# T09_LockBox_ver5.net
KiCad netlist of a schematic drawn in EAGLE
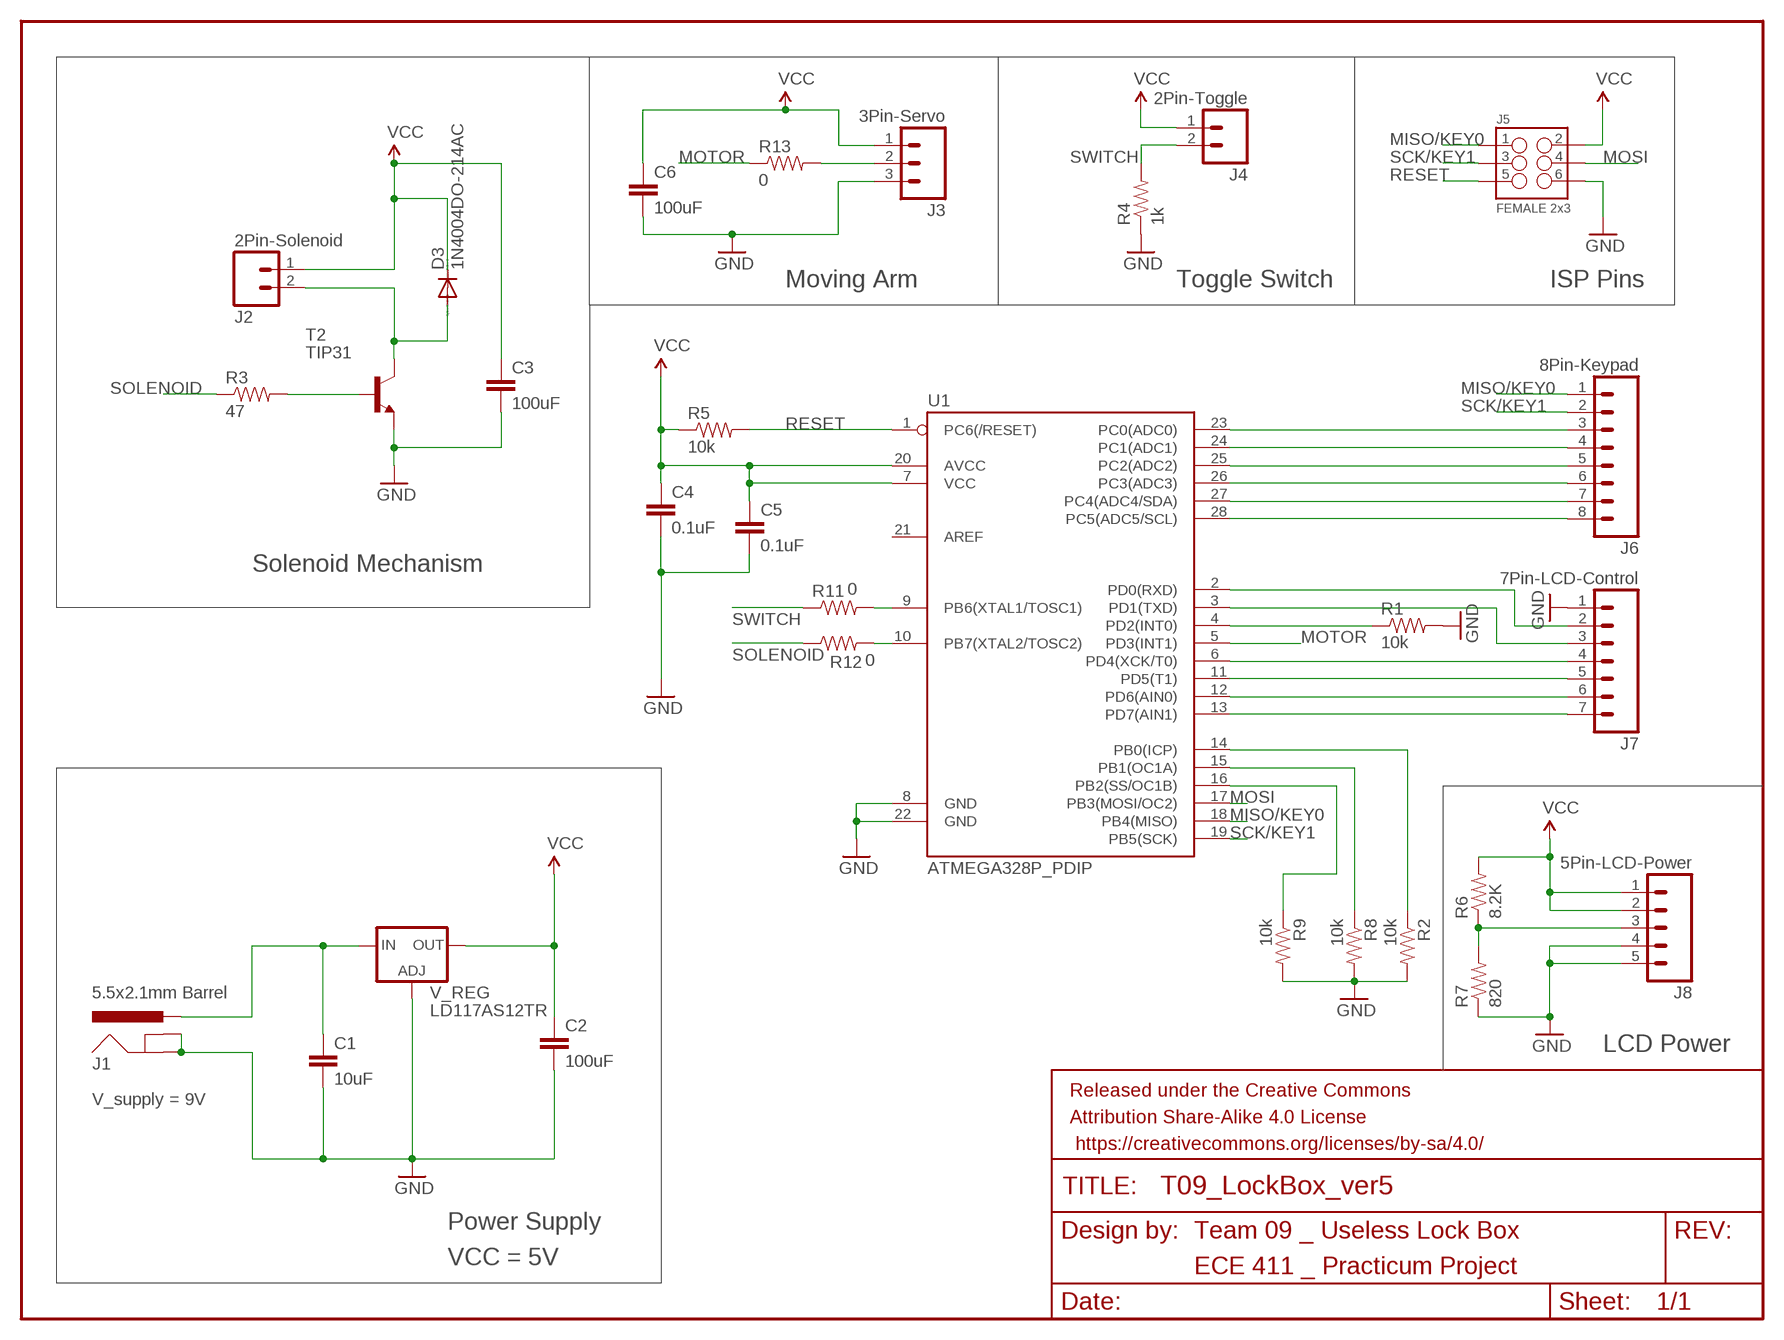
[diagram p0: schematic, sheet 1]

(export (version "E")
  (design (tool "Eeschema 10.0.6"))
  (components
    (comp (ref "C1")
      (value "10uF")
      (footprint "eagle-import:0603-CAP")
      (libsource (lib "eagle-import") (part "CAP0603-CAP"))
    )
    (comp (ref "C2")
      (value "100uF")
      (footprint "eagle-import:0603-CAP")
      (libsource (lib "eagle-import") (part "CAP0603-CAP"))
    )
    (comp (ref "C3")
      (value "100uF")
      (footprint "eagle-import:0603-CAP")
      (libsource (lib "eagle-import") (part "CAP0603-CAP"))
    )
    (comp (ref "C4")
      (value "0.1uF")
      (footprint "eagle-import:0603-CAP")
      (libsource (lib "eagle-import") (part "CAP0603-CAP"))
    )
    (comp (ref "C5")
      (value "0.1uF")
      (footprint "eagle-import:0603-CAP")
      (libsource (lib "eagle-import") (part "CAP0603-CAP"))
    )
    (comp (ref "C6")
      (value "100uF")
      (footprint "eagle-import:0603-CAP")
      (libsource (lib "eagle-import") (part "CAP0603-CAP"))
    )
    (comp (ref "CC_TEXT1")
      (value "CREATIVE_COMMONS")
      (footprint "eagle-import:CREATIVE_COMMONS")
      (libsource (lib "eagle-import") (part "CREATIVE_COMMONS"))
    )
    (comp (ref "D3")
      (value "1N4004DO-214AC")
      (footprint "eagle-import:DO-214AC")
      (libsource (lib "eagle-import") (part "1N4004DO-214AC"))
    )
    (comp (ref "FRAME1")
      (value "FRAME-LETTER")
      (footprint "eagle-import:CREATIVE_COMMONS")
      (libsource (lib "eagle-import") (part "FRAME-LETTER"))
    )
    (comp (ref "J1")
      (value "5.5x2.1mm Barrel")
      (footprint "eagle-import:POWER_JACK_SMD")
      (libsource (lib "eagle-import") (part "POWER_JACKSMD"))
    )
    (comp (ref "J2")
      (value "2Pin-Solenoid")
      (footprint "eagle-import:1X02")
      (libsource (lib "eagle-import") (part "M02PTH"))
    )
    (comp (ref "J3")
      (value "3Pin-Servo")
      (footprint "eagle-import:1X03")
      (libsource (lib "eagle-import") (part "M03PTH"))
    )
    (comp (ref "J4")
      (value "2Pin-Toggle")
      (footprint "eagle-import:1X02")
      (libsource (lib "eagle-import") (part "M02PTH"))
    )
    (comp (ref "J5")
      (value "FEMALE 2x3")
      (footprint "eagle-import:2X3")
      (libsource (lib "eagle-import") (part "M03X2FEMALE"))
    )
    (comp (ref "J6")
      (value "8Pin-Keypad")
      (footprint "eagle-import:1X08_ROUND")
      (libsource (lib "eagle-import") (part "M08"))
    )
    (comp (ref "J7")
      (value "7Pin-LCD-Control")
      (footprint "eagle-import:1X07")
      (libsource (lib "eagle-import") (part "M07"))
    )
    (comp (ref "J8")
      (value "5Pin-LCD-Power")
      (footprint "eagle-import:1X05")
      (libsource (lib "eagle-import") (part "M05PTH"))
    )
    (comp (ref "R1")
      (value "10k")
      (footprint "eagle-import:0603-RES")
      (libsource (lib "eagle-import") (part "RESISTOR0603"))
    )
    (comp (ref "R2")
      (value "10k")
      (footprint "eagle-import:0603-RES")
      (libsource (lib "eagle-import") (part "RESISTOR0603"))
    )
    (comp (ref "R3")
      (value "47")
      (footprint "eagle-import:0805")
      (libsource (lib "eagle-import") (part "RESISTOR0805-RES"))
    )
    (comp (ref "R4")
      (value "1k")
      (footprint "eagle-import:0603-RES")
      (libsource (lib "eagle-import") (part "RESISTOR0603"))
    )
    (comp (ref "R5")
      (value "10k")
      (footprint "eagle-import:0603-RES")
      (libsource (lib "eagle-import") (part "RESISTOR0603"))
    )
    (comp (ref "R6")
      (value "8.2K")
      (footprint "eagle-import:0603-RES")
      (libsource (lib "eagle-import") (part "RESISTOR0603"))
    )
    (comp (ref "R7")
      (value "820")
      (footprint "eagle-import:0603-RES")
      (libsource (lib "eagle-import") (part "RESISTOR0603"))
    )
    (comp (ref "R8")
      (value "10k")
      (footprint "eagle-import:0603-RES")
      (libsource (lib "eagle-import") (part "RESISTOR0603"))
    )
    (comp (ref "R9")
      (value "10k")
      (footprint "eagle-import:0603-RES")
      (libsource (lib "eagle-import") (part "RESISTOR0603"))
    )
    (comp (ref "R11")
      (value "0")
      (footprint "eagle-import:0603-RES")
      (libsource (lib "eagle-import") (part "RESISTOR0603"))
    )
    (comp (ref "R12")
      (value "0")
      (footprint "eagle-import:0603-RES")
      (libsource (lib "eagle-import") (part "RESISTOR0603"))
    )
    (comp (ref "R13")
      (value "0")
      (footprint "eagle-import:0603-RES")
      (libsource (lib "eagle-import") (part "RESISTOR0603"))
    )
    (comp (ref "T2")
      (value "TIP31")
      (footprint "eagle-import:TO220")
      (libsource (lib "eagle-import") (part "TIP31"))
    )
    (comp (ref "U1")
      (value "ATMEGA328P_PDIP")
      (footprint "eagle-import:DIL28-3")
      (libsource (lib "eagle-import") (part "ATMEGA328P_PDIP"))
    )
    (comp (ref "V_REG")
      (value "LD117AS12TR")
      (footprint "eagle-import:SOT223")
      (libsource (lib "eagle-import") (part "LD117A?S12TR"))
    )
  )
  (nets
    (net (code "1") (name "/MISO{slash}KEY0") (class "Default")
      (node (ref "J5") (pin "1") (pinfunction "1_1") (pintype "bidirectional"))
      (node (ref "J6") (pin "1") (pinfunction "1_1") (pintype "passive"))
      (node (ref "U1") (pin "18") (pinfunction "PB4(MISO)_18") (pintype "bidirectional"))
    )
    (net (code "2") (name "/MOSI") (class "Default")
      (node (ref "J5") (pin "4") (pinfunction "4_4") (pintype "bidirectional"))
      (node (ref "U1") (pin "17") (pinfunction "PB3(MOSI/OC2)_17") (pintype "bidirectional"))
    )
    (net (code "3") (name "/MOTOR") (class "Default")
      (node (ref "R13") (pin "1") (pinfunction "1_1") (pintype "passive"))
      (node (ref "U1") (pin "5") (pinfunction "PD3(INT1)_5") (pintype "bidirectional"))
    )
    (net (code "4") (name "/RESET") (class "Default")
      (node (ref "J5") (pin "5") (pinfunction "5_5") (pintype "bidirectional"))
      (node (ref "R5") (pin "2") (pinfunction "2_2") (pintype "passive"))
      (node (ref "U1") (pin "1") (pinfunction "PC6(/RESET)_1") (pintype "bidirectional"))
    )
    (net (code "5") (name "/SCK{slash}KEY1") (class "Default")
      (node (ref "J5") (pin "3") (pinfunction "3_3") (pintype "bidirectional"))
      (node (ref "J6") (pin "2") (pinfunction "2_2") (pintype "passive"))
      (node (ref "U1") (pin "19") (pinfunction "PB5(SCK)_19") (pintype "bidirectional"))
    )
    (net (code "6") (name "/SOLENOID") (class "Default")
      (node (ref "R12") (pin "1") (pinfunction "1_1") (pintype "passive"))
      (node (ref "R3") (pin "1") (pinfunction "1_1") (pintype "passive"))
    )
    (net (code "7") (name "/SWITCH") (class "Default")
      (node (ref "J4") (pin "2") (pinfunction "2_2") (pintype "passive"))
      (node (ref "R11") (pin "1") (pinfunction "1_1") (pintype "passive"))
      (node (ref "R4") (pin "2") (pinfunction "2_2") (pintype "passive"))
    )
    (net (code "8") (name "GND") (class "Default")
      (node (ref "C1") (pin "2") (pinfunction "2_2") (pintype "passive"))
      (node (ref "C2") (pin "2") (pinfunction "2_2") (pintype "passive"))
      (node (ref "C3") (pin "2") (pinfunction "2_2") (pintype "passive"))
      (node (ref "C4") (pin "2") (pinfunction "2_2") (pintype "passive"))
      (node (ref "C5") (pin "2") (pinfunction "2_2") (pintype "passive"))
      (node (ref "C6") (pin "2") (pinfunction "2_2") (pintype "passive"))
      (node (ref "J1") (pin "GND") (pinfunction "GNDBREAK_GND") (pintype "bidirectional"))
      (node (ref "J1") (pin "P$4") (pinfunction "GND_P$4") (pintype "bidirectional"))
      (node (ref "J3") (pin "3") (pinfunction "3_3") (pintype "passive"))
      (node (ref "J5") (pin "6") (pinfunction "6_6") (pintype "bidirectional"))
      (node (ref "J7") (pin "1") (pinfunction "1_1") (pintype "passive"))
      (node (ref "J8") (pin "4") (pinfunction "4_4") (pintype "passive"))
      (node (ref "J8") (pin "5") (pinfunction "5_5") (pintype "passive"))
      (node (ref "R1") (pin "2") (pinfunction "2_2") (pintype "passive"))
      (node (ref "R2") (pin "2") (pinfunction "2_2") (pintype "passive"))
      (node (ref "R4") (pin "1") (pinfunction "1_1") (pintype "passive"))
      (node (ref "R7") (pin "1") (pinfunction "1_1") (pintype "passive"))
      (node (ref "R8") (pin "2") (pinfunction "2_2") (pintype "passive"))
      (node (ref "R9") (pin "2") (pinfunction "2_2") (pintype "passive"))
      (node (ref "T2") (pin "3") (pinfunction "E_3") (pintype "passive"))
      (node (ref "U1") (pin "22") (pinfunction "GND_22") (pintype "bidirectional"))
      (node (ref "U1") (pin "8") (pinfunction "GND_8") (pintype "bidirectional"))
      (node (ref "V_REG") (pin "1") (pinfunction "ADJ_1") (pintype "input"))
    )
    (net (code "9") (name "Net-(J1-PWR)") (class "Default")
      (node (ref "C1") (pin "1") (pinfunction "1_1") (pintype "passive"))
      (node (ref "J1") (pin "VIN0") (pinfunction "PWR_VIN0") (pintype "bidirectional"))
      (node (ref "V_REG") (pin "3") (pinfunction "IN_3") (pintype "input"))
    )
    (net (code "10") (name "Net-(J3-Pad2)") (class "Default")
      (node (ref "J3") (pin "2") (pinfunction "2_2") (pintype "passive"))
      (node (ref "R13") (pin "2") (pinfunction "2_2") (pintype "passive"))
    )
    (net (code "11") (name "Net-(J8-Pad3)") (class "Default")
      (node (ref "J8") (pin "3") (pinfunction "3_3") (pintype "passive"))
      (node (ref "R6") (pin "1") (pinfunction "1_1") (pintype "passive"))
      (node (ref "R7") (pin "2") (pinfunction "2_2") (pintype "passive"))
    )
    (net (code "12") (name "Net-(T2-B)") (class "Default")
      (node (ref "R3") (pin "2") (pinfunction "2_2") (pintype "passive"))
      (node (ref "T2") (pin "1") (pinfunction "B_1") (pintype "passive"))
    )
    (net (code "13") (name "Net-(T2-C)") (class "Default")
      (node (ref "D3") (pin "A") (pinfunction "A_A") (pintype "passive"))
      (node (ref "J2") (pin "2") (pinfunction "2_2") (pintype "passive"))
      (node (ref "T2") (pin "2") (pinfunction "C_2") (pintype "passive"))
    )
    (net (code "14") (name "Net-(U1-PB0(ICP))") (class "Default")
      (node (ref "R2") (pin "1") (pinfunction "1_1") (pintype "passive"))
      (node (ref "U1") (pin "14") (pinfunction "PB0(ICP)_14") (pintype "bidirectional"))
    )
    (net (code "15") (name "Net-(U1-PB1(OC1A))") (class "Default")
      (node (ref "R8") (pin "1") (pinfunction "1_1") (pintype "passive"))
      (node (ref "U1") (pin "15") (pinfunction "PB1(OC1A)_15") (pintype "bidirectional"))
    )
    (net (code "16") (name "Net-(U1-PB2(SS{slash}OC1B))") (class "Default")
      (node (ref "R9") (pin "1") (pinfunction "1_1") (pintype "passive"))
      (node (ref "U1") (pin "16") (pinfunction "PB2(SS/OC1B)_16") (pintype "bidirectional"))
    )
    (net (code "17") (name "Net-(U1-PB6(XTAL1{slash}TOSC1))") (class "Default")
      (node (ref "R11") (pin "2") (pinfunction "2_2") (pintype "passive"))
      (node (ref "U1") (pin "9") (pinfunction "PB6(XTAL1/TOSC1)_9") (pintype "bidirectional"))
    )
    (net (code "18") (name "Net-(U1-PB7(XTAL2{slash}TOSC2))") (class "Default")
      (node (ref "R12") (pin "2") (pinfunction "2_2") (pintype "passive"))
      (node (ref "U1") (pin "10") (pinfunction "PB7(XTAL2/TOSC2)_10") (pintype "bidirectional"))
    )
    (net (code "19") (name "Net-(U1-PC0(ADC0))") (class "Default")
      (node (ref "J6") (pin "3") (pinfunction "3_3") (pintype "passive"))
      (node (ref "U1") (pin "23") (pinfunction "PC0(ADC0)_23") (pintype "bidirectional"))
    )
    (net (code "20") (name "Net-(U1-PC1(ADC1))") (class "Default")
      (node (ref "J6") (pin "4") (pinfunction "4_4") (pintype "passive"))
      (node (ref "U1") (pin "24") (pinfunction "PC1(ADC1)_24") (pintype "bidirectional"))
    )
    (net (code "21") (name "Net-(U1-PC2(ADC2))") (class "Default")
      (node (ref "J6") (pin "5") (pinfunction "5_5") (pintype "passive"))
      (node (ref "U1") (pin "25") (pinfunction "PC2(ADC2)_25") (pintype "bidirectional"))
    )
    (net (code "22") (name "Net-(U1-PC3(ADC3))") (class "Default")
      (node (ref "J6") (pin "6") (pinfunction "6_6") (pintype "passive"))
      (node (ref "U1") (pin "26") (pinfunction "PC3(ADC3)_26") (pintype "bidirectional"))
    )
    (net (code "23") (name "Net-(U1-PC4(ADC4{slash}SDA))") (class "Default")
      (node (ref "J6") (pin "7") (pinfunction "7_7") (pintype "passive"))
      (node (ref "U1") (pin "27") (pinfunction "PC4(ADC4/SDA)_27") (pintype "bidirectional"))
    )
    (net (code "24") (name "Net-(U1-PC5(ADC5{slash}SCL))") (class "Default")
      (node (ref "J6") (pin "8") (pinfunction "8_8") (pintype "passive"))
      (node (ref "U1") (pin "28") (pinfunction "PC5(ADC5/SCL)_28") (pintype "bidirectional"))
    )
    (net (code "25") (name "Net-(U1-PD0(RXD))") (class "Default")
      (node (ref "J7") (pin "2") (pinfunction "2_2") (pintype "passive"))
      (node (ref "U1") (pin "2") (pinfunction "PD0(RXD)_2") (pintype "bidirectional"))
    )
    (net (code "26") (name "Net-(U1-PD1(TXD))") (class "Default")
      (node (ref "J7") (pin "3") (pinfunction "3_3") (pintype "passive"))
      (node (ref "U1") (pin "3") (pinfunction "PD1(TXD)_3") (pintype "bidirectional"))
    )
    (net (code "27") (name "Net-(U1-PD2(INT0))") (class "Default")
      (node (ref "R1") (pin "1") (pinfunction "1_1") (pintype "passive"))
      (node (ref "U1") (pin "4") (pinfunction "PD2(INT0)_4") (pintype "bidirectional"))
    )
    (net (code "28") (name "Net-(U1-PD4(XCK{slash}T0))") (class "Default")
      (node (ref "J7") (pin "4") (pinfunction "4_4") (pintype "passive"))
      (node (ref "U1") (pin "6") (pinfunction "PD4(XCK/T0)_6") (pintype "bidirectional"))
    )
    (net (code "29") (name "Net-(U1-PD5(T1))") (class "Default")
      (node (ref "J7") (pin "5") (pinfunction "5_5") (pintype "passive"))
      (node (ref "U1") (pin "11") (pinfunction "PD5(T1)_11") (pintype "bidirectional"))
    )
    (net (code "30") (name "Net-(U1-PD6(AIN0))") (class "Default")
      (node (ref "J7") (pin "6") (pinfunction "6_6") (pintype "passive"))
      (node (ref "U1") (pin "12") (pinfunction "PD6(AIN0)_12") (pintype "bidirectional"))
    )
    (net (code "31") (name "Net-(U1-PD7(AIN1))") (class "Default")
      (node (ref "J7") (pin "7") (pinfunction "7_7") (pintype "passive"))
      (node (ref "U1") (pin "13") (pinfunction "PD7(AIN1)_13") (pintype "bidirectional"))
    )
    (net (code "32") (name "VCC") (class "Default")
      (node (ref "C2") (pin "1") (pinfunction "1_1") (pintype "passive"))
      (node (ref "C3") (pin "1") (pinfunction "1_1") (pintype "passive"))
      (node (ref "C4") (pin "1") (pinfunction "1_1") (pintype "passive"))
      (node (ref "C5") (pin "1") (pinfunction "1_1") (pintype "passive"))
      (node (ref "C6") (pin "1") (pinfunction "1_1") (pintype "passive"))
      (node (ref "D3") (pin "C") (pinfunction "C_C") (pintype "passive"))
      (node (ref "J2") (pin "1") (pinfunction "1_1") (pintype "passive"))
      (node (ref "J3") (pin "1") (pinfunction "1_1") (pintype "passive"))
      (node (ref "J4") (pin "1") (pinfunction "1_1") (pintype "passive"))
      (node (ref "J5") (pin "2") (pinfunction "2_2") (pintype "bidirectional"))
      (node (ref "J8") (pin "1") (pinfunction "1_1") (pintype "passive"))
      (node (ref "J8") (pin "2") (pinfunction "2_2") (pintype "passive"))
      (node (ref "R5") (pin "1") (pinfunction "1_1") (pintype "passive"))
      (node (ref "R6") (pin "2") (pinfunction "2_2") (pintype "passive"))
      (node (ref "U1") (pin "20") (pinfunction "AVCC_20") (pintype "bidirectional"))
      (node (ref "U1") (pin "7") (pinfunction "VCC_7") (pintype "bidirectional"))
      (node (ref "V_REG") (pin "4") (pinfunction "OUT_4") (pintype "passive"))
    )
    (net (code "33") (name "unconnected-(U1-AREF-Pad21)") (class "Default")
      (node (ref "U1") (pin "21") (pinfunction "AREF_21") (pintype "bidirectional"))
    )
  )
)
